# AICat.net
KiCad netlist of a schematic drawn in Altium Designer
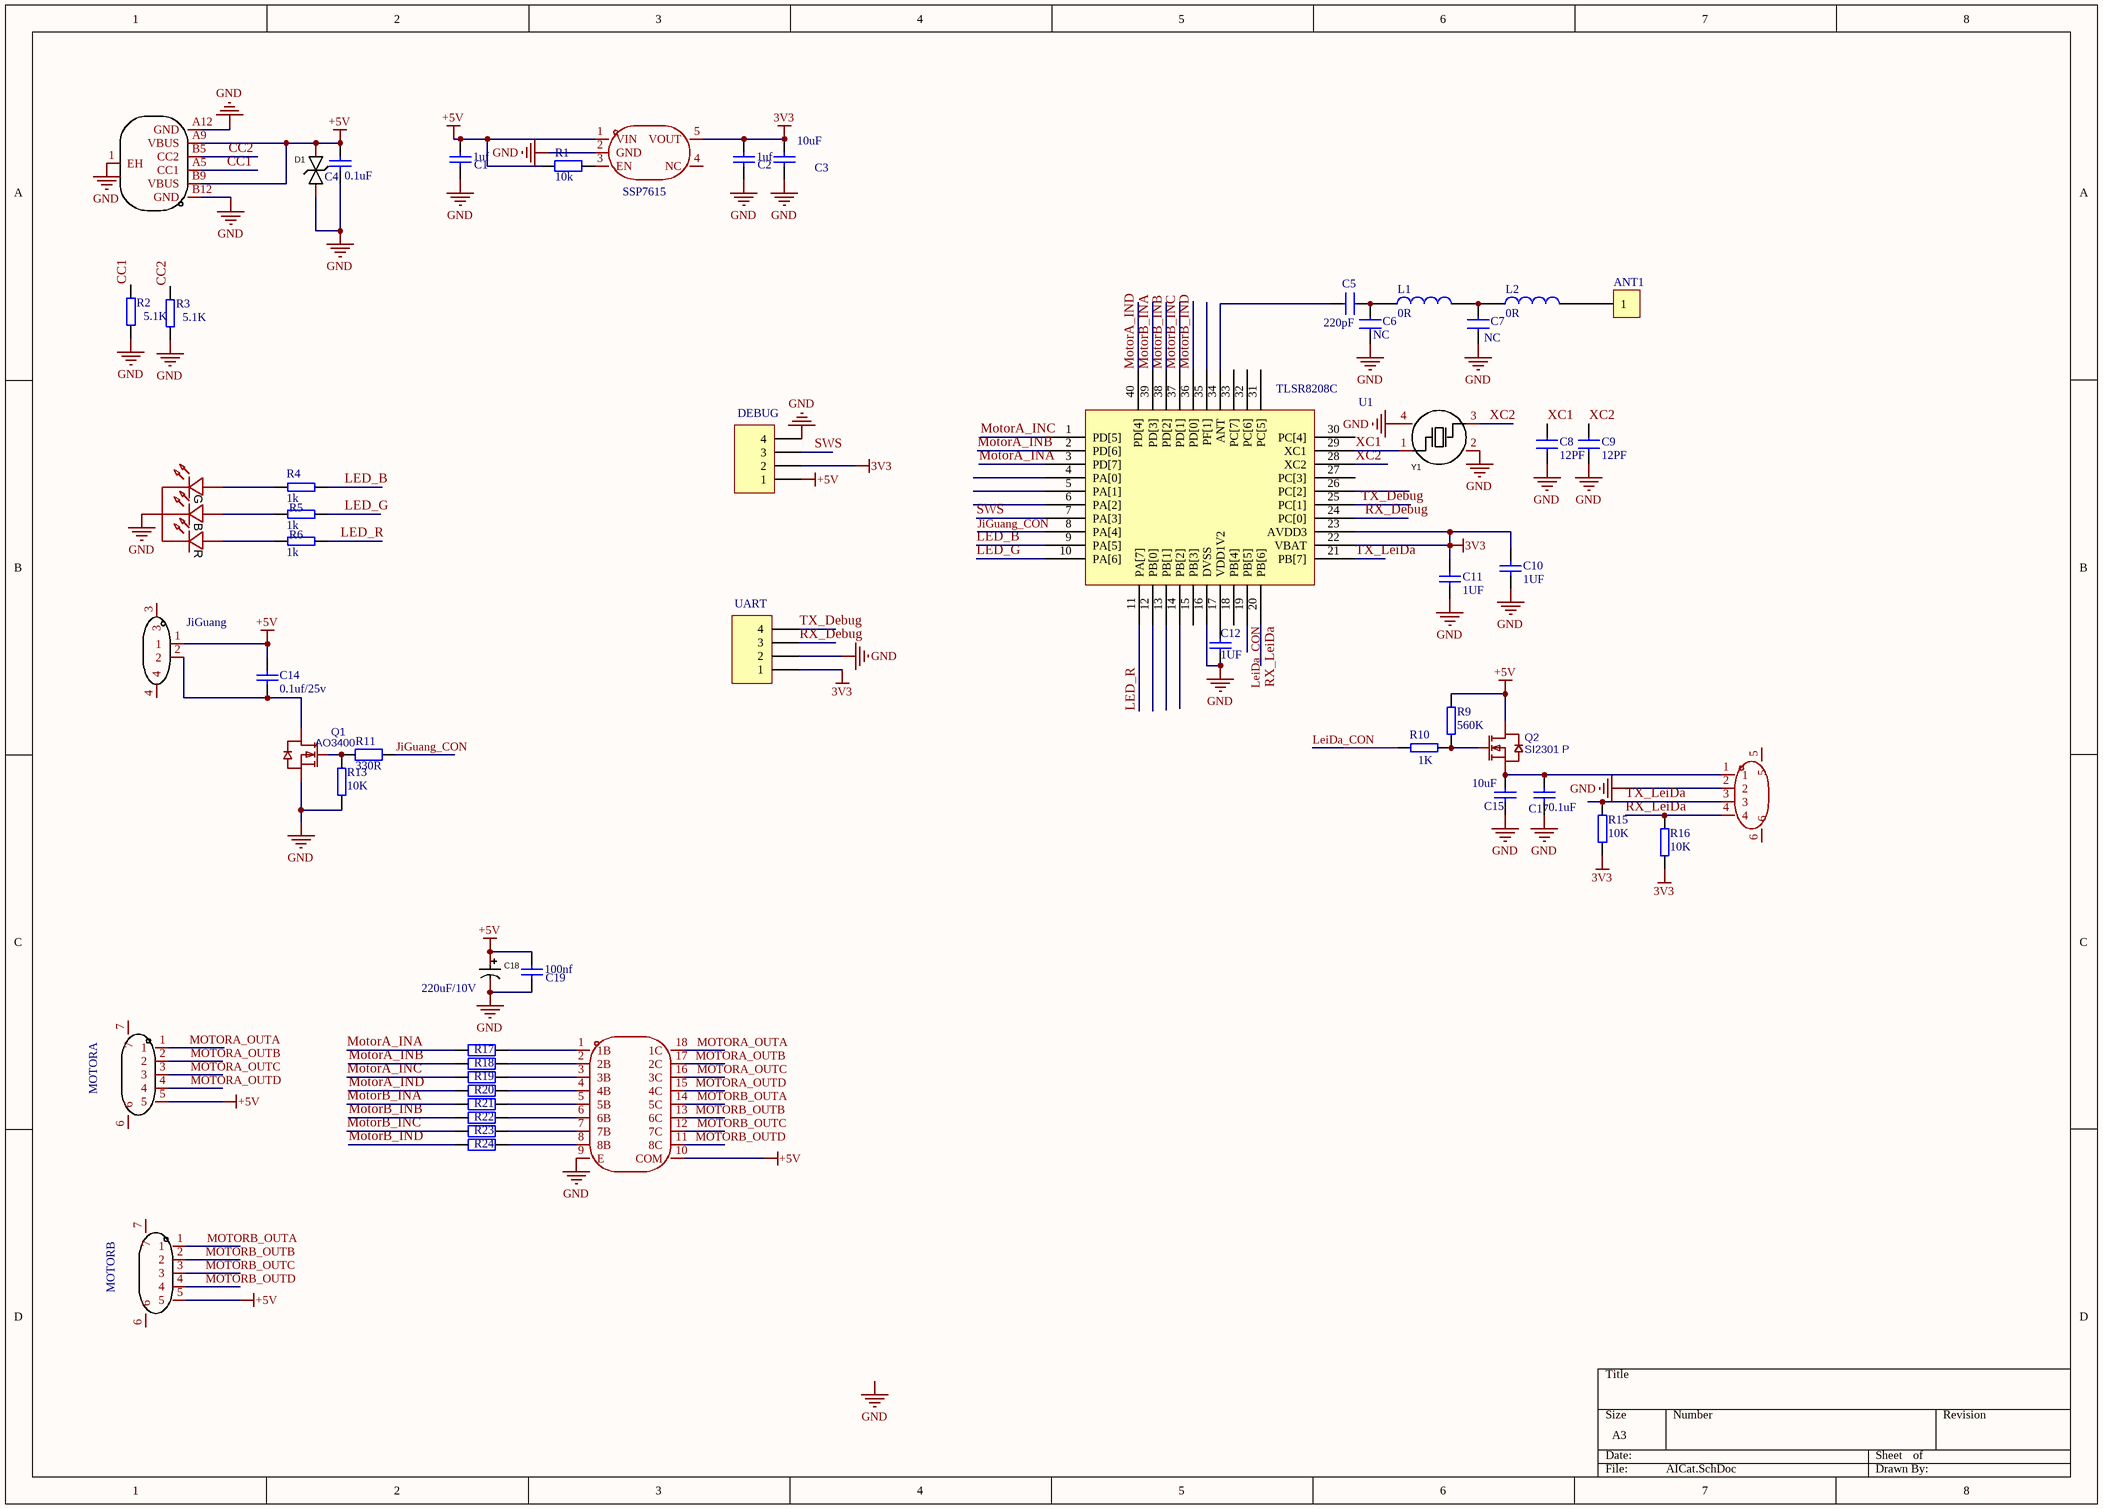
[diagram p0: AICat.SchDoc]

(export (version "E")
  (design (tool "Eeschema 10.0.6"))
  (components
    (comp (ref "ANT1")
      (value "~")
      (footprint "tp")
      (description "Connector")
      (libsource (lib "*") (part "CON1"))
    )
    (comp (ref "C1")
      (value "1uf")
      (footprint "0603_C")
      (description "无极电容")
      (libsource (lib "电容电阻电感保险") (part "Cap1"))
    )
    (comp (ref "C2")
      (value "1uf")
      (footprint "0603_C")
      (description "无极电容")
      (libsource (lib "电容电阻电感保险") (part "Cap1"))
    )
    (comp (ref "C3")
      (value "10uF")
      (footprint "0805_C")
      (description "Capacitor")
      (fields (field (name "PUBLISHER") "Altium Limited"))
      (libsource (lib "*") (part "Cap"))
    )
    (comp (ref "C4")
      (value "0.1uF")
      (footprint "0603_C")
      (description "Capacitor")
      (fields (field (name "PUBLISHER") "Altium Limited"))
      (libsource (lib "*") (part "Cap"))
    )
    (comp (ref "C5")
      (value "220pF")
      (footprint "0603_c")
      (description "Capacitor")
      (libsource (lib "*") (part "CAP"))
    )
    (comp (ref "C6")
      (value "NC")
      (footprint "0603_c")
      (description "Capacitor")
      (libsource (lib "*") (part "CAP"))
    )
    (comp (ref "C7")
      (value "NC")
      (footprint "0603_c")
      (description "Capacitor")
      (libsource (lib "*") (part "CAP"))
    )
    (comp (ref "C8")
      (value "12PF")
      (footprint "0603_c")
      (description "Capacitor")
      (libsource (lib "*") (part "CAP"))
    )
    (comp (ref "C9")
      (value "12PF")
      (footprint "0603_c")
      (description "Capacitor")
      (libsource (lib "*") (part "CAP"))
    )
    (comp (ref "C10") (value "1UF") (footprint "0603_c") (libsource (lib "DIY") (part "CAP")))
    (comp (ref "C11") (value "1UF") (footprint "0603_c") (libsource (lib "DIY") (part "CAP")))
    (comp (ref "C12") (value "1UF") (footprint "0603_c") (libsource (lib "DIY") (part "CAP")))
    (comp (ref "C14")
      (value "0.1uf/25v")
      (footprint "0603_C")
      (description "Capacitor")
      (fields (field (name "PUBLISHER") "Altium Limited"))
      (libsource (lib "*") (part "Cap"))
    )
    (comp (ref "C15")
      (value "10uF")
      (footprint "0805_C")
      (description "Capacitor")
      (fields (field (name "PUBLISHER") "Altium Limited"))
      (libsource (lib "*") (part "Cap"))
    )
    (comp (ref "C17")
      (value "0.1uF")
      (footprint "0603_C")
      (description "Capacitor")
      (fields (field (name "PUBLISHER") "Altium Limited"))
      (libsource (lib "*") (part "Cap"))
    )
    (comp (ref "C18")
      (value "220uF/10V")
      (footprint "SMD 6.3*5.4 电解")
      (fields (field (name "MANUFACTURER PART") "RVT1A221M0605"))
      (libsource (lib "altium-import") (part "root_0_RVT1A221M0605_C72494_"))
    )
    (comp (ref "C19")
      (value "100nf")
      (footprint "0603_C")
      (description "无极电容")
      (libsource (lib "电容电阻电感保险") (part "Cap1"))
    )
    (comp (ref "CN2")
      (value "JiGuang")
      (footprint "CONN-SMD_2P-P1.25-LT")
      (fields (field (name "MANUFACTURER PART") "HC-1.25-2PLT"))
      (libsource (lib "altium-import") (part "root_0_mirrored_HC-1.25-2PLT_"))
    )
    (comp (ref "CN4")
      (value "HC-1.25-4PLT")
      (footprint "CONN-SMD_4P-P1.25_LT")
      (libsource (lib "altium-import") (part "root_0_HC-1.25-4PLT_"))
    )
    (comp (ref "D1")
      (value "SMF5.0CA_C726939")
      (footprint "SOD-123 双向")
      (fields (field (name "MANUFACTURER PART") "SMF5.0CA"))
      (libsource (lib "altium-import") (part "root_1_SMF5.0CA_C726939_"))
    )
    (comp (ref "J1")
      (value "MOTORA")
      (footprint "CONN-SMD_1.25-5PLT")
      (fields (field (name "MANUFACTURER PART") "HC-1.25-5PLT"))
      (libsource (lib "altium-import") (part "root_0_mirrored_HC-1.25-5PLT_"))
    )
    (comp (ref "J2")
      (value "MOTORB")
      (footprint "CONN-SMD_1.25-5PLT")
      (fields (field (name "MANUFACTURER PART") "HC-1.25-5PLT"))
      (libsource (lib "altium-import") (part "root_0_mirrored_HC-1.25-5PLT_"))
    )
    (comp (ref "L1") (value "0R") (footprint "0603_r") (libsource (lib "*") (part "INDUCTOR")))
    (comp (ref "L2") (value "0R") (footprint "0603_r") (libsource (lib "*") (part "INDUCTOR")))
    (comp (ref "LED1")
      (value "MHSC110RGBCT")
      (footprint "LED-SMD_4P-L3.0-W1.5-L")
      (libsource (lib "altium-import") (part "root_3_MHSC110RGBCT_"))
    )
    (comp (ref "P1")
      (value "DEBUG")
      (footprint "SIP4-2.54")
      (description "Header, 4-Pin")
      (fields (field (name "PUBLISHER") "Altium Limited"))
      (libsource (lib "Miscellaneous Connectors") (part "Header 4"))
    )
    (comp (ref "P2")
      (value "UART")
      (footprint "SIP4-2.54")
      (description "Header, 4-Pin")
      (fields (field (name "PUBLISHER") "Altium Limited"))
      (libsource (lib "Miscellaneous Connectors") (part "Header 4"))
    )
    (comp (ref "Q1")
      (value "AO3400")
      (footprint "SOT-23")
      (fields
        (field (name "BOM_SUPPLIER PART") "C2890442")
        (field (name "BOM_MANUFACTURER PART") "JMTL3400A")
        (field (name "CONTRIBUTOR") "LCSC")
      )
      (libsource (lib "altium-import") (part "root_0_mirrored_JMTL3400A_"))
    )
    (comp (ref "Q2")
      (value "SI2301 P")
      (footprint "SOT-23")
      (fields
        (field (name "BOM_SUPPLIER PART") "C2890442")
        (field (name "BOM_MANUFACTURER PART") "JMTL3400A")
        (field (name "CONTRIBUTOR") "LCSC")
      )
      (libsource (lib "altium-import") (part "root_0_JMTL3400A_"))
    )
    (comp (ref "R1")
      (value "10k")
      (footprint "0603_R")
      (description "Resistor")
      (fields (field (name "PUBLISHER") "Altium Limited"))
      (libsource (lib "*") (part "Res2"))
    )
    (comp (ref "R2") (value "5.1K") (footprint "0603_R") (libsource (lib "DIY") (part "RES")))
    (comp (ref "R3") (value "5.1K") (footprint "0603_R") (libsource (lib "DIY") (part "RES")))
    (comp (ref "R4") (value "1k") (footprint "0603_R") (libsource (lib "DIY") (part "RES")))
    (comp (ref "R5") (value "1k") (footprint "0603_R") (libsource (lib "DIY") (part "RES")))
    (comp (ref "R6") (value "1k") (footprint "0603_R") (libsource (lib "DIY") (part "RES")))
    (comp (ref "R9") (value "560K") (footprint "0603_R") (libsource (lib "*") (part "RES")))
    (comp (ref "R10") (value "1K") (footprint "0603_R") (libsource (lib "") (part "RES_1")))
    (comp (ref "R11")
      (value "330R")
      (footprint "0603_R")
      (description "Resistor")
      (fields (field (name "PUBLISHER") "Altium Limited"))
      (libsource (lib "") (part "Res2_2"))
    )
    (comp (ref "R13") (value "10K") (footprint "0603_R") (libsource (lib "DIY") (part "RES")))
    (comp (ref "R15") (value "10K") (footprint "0603_R") (libsource (lib "*") (part "RES")))
    (comp (ref "R16") (value "10K") (footprint "0603_R") (libsource (lib "*") (part "RES")))
    (comp (ref "R17")
      (value "330R")
      (footprint "0603_R")
      (description "Resistor")
      (fields (field (name "PUBLISHER") "Altium Limited"))
      (libsource (lib "") (part "Res2_1"))
    )
    (comp (ref "R18")
      (value "330R")
      (footprint "0603_R")
      (description "Resistor")
      (fields (field (name "PUBLISHER") "Altium Limited"))
      (libsource (lib "") (part "Res2_1"))
    )
    (comp (ref "R19")
      (value "330R")
      (footprint "0603_R")
      (description "Resistor")
      (fields (field (name "PUBLISHER") "Altium Limited"))
      (libsource (lib "") (part "Res2_1"))
    )
    (comp (ref "R20")
      (value "330R")
      (footprint "0603_R")
      (description "Resistor")
      (fields (field (name "PUBLISHER") "Altium Limited"))
      (libsource (lib "") (part "Res2_1"))
    )
    (comp (ref "R21")
      (value "330R")
      (footprint "0603_R")
      (description "Resistor")
      (fields (field (name "PUBLISHER") "Altium Limited"))
      (libsource (lib "") (part "Res2_1"))
    )
    (comp (ref "R22")
      (value "330R")
      (footprint "0603_R")
      (description "Resistor")
      (fields (field (name "PUBLISHER") "Altium Limited"))
      (libsource (lib "") (part "Res2_1"))
    )
    (comp (ref "R23")
      (value "330R")
      (footprint "0603_R")
      (description "Resistor")
      (fields (field (name "PUBLISHER") "Altium Limited"))
      (libsource (lib "") (part "Res2_1"))
    )
    (comp (ref "R24")
      (value "330R")
      (footprint "0603_R")
      (description "Resistor")
      (fields (field (name "PUBLISHER") "Altium Limited"))
      (libsource (lib "") (part "Res2_1"))
    )
    (comp (ref "U1")
      (value "TLSR8208C")
      (footprint "QFN-40_L5.0-W5.0-P0.40-BL-EP3.7")
      (libsource (lib "MyLib") (part "TLSR8208C"))
    )
    (comp (ref "U2")
      (value "ULN2803A")
      (footprint "SOIC-18_L11.6-W7.5-P1.27-LS10.3-BL")
      (libsource (lib "altium-import") (part "root_0_ULN2803A_C181731_"))
    )
    (comp (ref "U4")
      (value "SSP7615")
      (footprint "SOT-23-5")
      (libsource (lib "altium-import") (part "root_0_SSP7615-33M5R_"))
    )
    (comp (ref "USB1")
      (value "TYPE-C 6P")
      (footprint "TPYE-C-6")
      (fields (field (name "MANUFACTURER PART") "TYPE-C 6P LTH6.5"))
      (libsource (lib "altium-import") (part "root_2_TYPE-C 6P LTH6.5_"))
    )
    (comp (ref "Y1")
      (value "24MHz +-20PPM")
      (footprint "CRYSTAL-SMD_4P-L3.2-W2.5")
      (fields (field (name "MANUFACTURER PART") "TAXM13.56M4RLBCCT2T"))
      (libsource (lib "altium-import") (part "root_0_TAXM13.56M4RLBCCT2T_"))
    )
  )
  (nets
    (net (code "1") (name "+5V") (class "Default")
      (node (ref "C1") (pin "2") (pinfunction "2_2") (pintype "passive"))
      (node (ref "C14") (pin "2") (pinfunction "2_2") (pintype "passive"))
      (node (ref "C18") (pin "1") (pinfunction "1_1") (pintype "passive"))
      (node (ref "C19") (pin "2") (pinfunction "2_2") (pintype "passive"))
      (node (ref "C4") (pin "2") (pinfunction "2_2") (pintype "passive"))
      (node (ref "CN2") (pin "1") (pinfunction "1_1") (pintype "passive"))
      (node (ref "D1") (pin "2") (pinfunction "2_2") (pintype "passive"))
      (node (ref "J1") (pin "5") (pinfunction "5_5") (pintype "passive"))
      (node (ref "J2") (pin "5") (pinfunction "5_5") (pintype "passive"))
      (node (ref "P1") (pin "1") (pinfunction "1_1") (pintype "passive"))
      (node (ref "Q2") (pin "2") (pinfunction "D_2") (pintype "passive"))
      (node (ref "R1") (pin "1") (pinfunction "1_1") (pintype "passive"))
      (node (ref "R9") (pin "1") (pintype "passive"))
      (node (ref "U2") (pin "10") (pinfunction "COM_10") (pintype "passive"))
      (node (ref "U4") (pin "1") (pinfunction "VIN_1") (pintype "passive"))
      (node (ref "USB1") (pin "A9") (pinfunction "VBUS_A9") (pintype "passive"))
      (node (ref "USB1") (pin "B9") (pinfunction "VBUS_B9") (pintype "passive"))
    )
    (net (code "2") (name "/CC1") (class "Default")
      (node (ref "R2") (pin "1") (pinfunction "1_1") (pintype "passive"))
      (node (ref "USB1") (pin "A5") (pinfunction "CC1_A5") (pintype "passive"))
    )
    (net (code "3") (name "/CC2") (class "Default")
      (node (ref "R3") (pin "1") (pinfunction "1_1") (pintype "passive"))
      (node (ref "USB1") (pin "B5") (pinfunction "CC2_B5") (pintype "passive"))
    )
    (net (code "4") (name "/JiGuang_CON") (class "Default")
      (node (ref "R11") (pin "2") (pinfunction "2_2") (pintype "passive"))
      (node (ref "U1") (pin "8") (pinfunction "PA[4]_8") (pintype "passive"))
    )
    (net (code "5") (name "/LED_B") (class "Default")
      (node (ref "R4") (pin "2") (pinfunction "2_2") (pintype "passive"))
      (node (ref "U1") (pin "9") (pinfunction "PA[5]_9") (pintype "passive"))
    )
    (net (code "6") (name "/LED_G") (class "Default")
      (node (ref "R5") (pin "2") (pinfunction "2_2") (pintype "passive"))
      (node (ref "U1") (pin "10") (pinfunction "PA[6]_10") (pintype "passive"))
    )
    (net (code "7") (name "/LED_R") (class "Default")
      (node (ref "R6") (pin "2") (pinfunction "2_2") (pintype "passive"))
      (node (ref "U1") (pin "11") (pinfunction "PA[7]_11") (pintype "passive"))
    )
    (net (code "8") (name "/LeiDa_CON") (class "Default")
      (node (ref "R10") (pin "2") (pintype "passive"))
      (node (ref "U1") (pin "19") (pinfunction "PB[5]_19") (pintype "passive"))
    )
    (net (code "9") (name "/MOTORA_OUTA") (class "Default")
      (node (ref "J1") (pin "1") (pinfunction "1_1") (pintype "passive"))
      (node (ref "U2") (pin "18") (pinfunction "1C_18") (pintype "passive"))
    )
    (net (code "10") (name "/MOTORA_OUTB") (class "Default")
      (node (ref "J1") (pin "2") (pinfunction "2_2") (pintype "passive"))
      (node (ref "U2") (pin "17") (pinfunction "2C_17") (pintype "passive"))
    )
    (net (code "11") (name "/MOTORA_OUTC") (class "Default")
      (node (ref "J1") (pin "3") (pinfunction "3_3") (pintype "passive"))
      (node (ref "U2") (pin "16") (pinfunction "3C_16") (pintype "passive"))
    )
    (net (code "12") (name "/MOTORA_OUTD") (class "Default")
      (node (ref "J1") (pin "4") (pinfunction "4_4") (pintype "passive"))
      (node (ref "U2") (pin "15") (pinfunction "4C_15") (pintype "passive"))
    )
    (net (code "13") (name "/MOTORB_OUTA") (class "Default")
      (node (ref "J2") (pin "1") (pinfunction "1_1") (pintype "passive"))
      (node (ref "U2") (pin "14") (pinfunction "5C_14") (pintype "passive"))
    )
    (net (code "14") (name "/MOTORB_OUTB") (class "Default")
      (node (ref "J2") (pin "2") (pinfunction "2_2") (pintype "passive"))
      (node (ref "U2") (pin "13") (pinfunction "6C_13") (pintype "passive"))
    )
    (net (code "15") (name "/MOTORB_OUTC") (class "Default")
      (node (ref "J2") (pin "3") (pinfunction "3_3") (pintype "passive"))
      (node (ref "U2") (pin "12") (pinfunction "7C_12") (pintype "passive"))
    )
    (net (code "16") (name "/MOTORB_OUTD") (class "Default")
      (node (ref "J2") (pin "4") (pinfunction "4_4") (pintype "passive"))
      (node (ref "U2") (pin "11") (pinfunction "8C_11") (pintype "passive"))
    )
    (net (code "17") (name "/MotorA_INA") (class "Default")
      (node (ref "R17") (pin "2") (pinfunction "2_2") (pintype "passive"))
      (node (ref "U1") (pin "3") (pinfunction "PD[7]_3") (pintype "passive"))
    )
    (net (code "18") (name "/MotorA_INB") (class "Default")
      (node (ref "R18") (pin "2") (pinfunction "2_2") (pintype "passive"))
      (node (ref "U1") (pin "2") (pinfunction "PD[6]_2") (pintype "passive"))
    )
    (net (code "19") (name "/MotorA_INC") (class "Default")
      (node (ref "R19") (pin "2") (pinfunction "2_2") (pintype "passive"))
      (node (ref "U1") (pin "1") (pinfunction "PD[5]_1") (pintype "passive"))
    )
    (net (code "20") (name "/MotorA_IND") (class "Default")
      (node (ref "R20") (pin "2") (pinfunction "2_2") (pintype "passive"))
      (node (ref "U1") (pin "40") (pinfunction "PD[4]_40") (pintype "passive"))
    )
    (net (code "21") (name "/MotorB_INA") (class "Default")
      (node (ref "R21") (pin "2") (pinfunction "2_2") (pintype "passive"))
      (node (ref "U1") (pin "39") (pinfunction "PD[3]_39") (pintype "passive"))
    )
    (net (code "22") (name "/MotorB_INB") (class "Default")
      (node (ref "R22") (pin "2") (pinfunction "2_2") (pintype "passive"))
      (node (ref "U1") (pin "38") (pinfunction "PD[2]_38") (pintype "passive"))
    )
    (net (code "23") (name "/MotorB_INC") (class "Default")
      (node (ref "R23") (pin "2") (pinfunction "2_2") (pintype "passive"))
      (node (ref "U1") (pin "37") (pinfunction "PD[1]_37") (pintype "passive"))
    )
    (net (code "24") (name "/MotorB_IND") (class "Default")
      (node (ref "R24") (pin "2") (pinfunction "2_2") (pintype "passive"))
      (node (ref "U1") (pin "36") (pinfunction "PD[0]_36") (pintype "passive"))
    )
    (net (code "25") (name "/RX_Debug") (class "Default")
      (node (ref "P2") (pin "3") (pinfunction "3_3") (pintype "passive"))
      (node (ref "U1") (pin "24") (pinfunction "PC[0]_24") (pintype "passive"))
    )
    (net (code "26") (name "/RX_LeiDa") (class "Default")
      (node (ref "CN4") (pin "4") (pinfunction "4_4") (pintype "passive"))
      (node (ref "R16") (pin "1") (pintype "passive"))
      (node (ref "U1") (pin "20") (pinfunction "PB[6]_20") (pintype "passive"))
    )
    (net (code "27") (name "/SWS") (class "Default")
      (node (ref "P1") (pin "3") (pinfunction "3_3") (pintype "passive"))
      (node (ref "U1") (pin "7") (pinfunction "PA[3]_7") (pintype "passive"))
    )
    (net (code "28") (name "/TX_Debug") (class "Default")
      (node (ref "P2") (pin "4") (pinfunction "4_4") (pintype "passive"))
      (node (ref "U1") (pin "25") (pinfunction "PC[1]_25") (pintype "passive"))
    )
    (net (code "29") (name "/TX_LeiDa") (class "Default")
      (node (ref "CN4") (pin "3") (pinfunction "3_3") (pintype "passive"))
      (node (ref "R15") (pin "1") (pintype "passive"))
      (node (ref "U1") (pin "21") (pinfunction "PB[7]_21") (pintype "passive"))
    )
    (net (code "30") (name "/XC1") (class "Default")
      (node (ref "C8") (pin "2") (pinfunction "2_2") (pintype "passive"))
      (node (ref "U1") (pin "29") (pinfunction "XC1_29") (pintype "passive"))
      (node (ref "Y1") (pin "1") (pinfunction "OSC1_1") (pintype "passive"))
    )
    (net (code "31") (name "/XC2") (class "Default")
      (node (ref "C9") (pin "2") (pinfunction "2_2") (pintype "passive"))
      (node (ref "U1") (pin "28") (pinfunction "XC2_28") (pintype "passive"))
      (node (ref "Y1") (pin "3") (pinfunction "OSC2_3") (pintype "passive"))
    )
    (net (code "32") (name "3V3") (class "Default")
      (node (ref "C10") (pin "1") (pintype "passive"))
      (node (ref "C11") (pin "1") (pintype "passive"))
      (node (ref "C2") (pin "2") (pinfunction "2_2") (pintype "passive"))
      (node (ref "C3") (pin "2") (pinfunction "2_2") (pintype "passive"))
      (node (ref "P1") (pin "2") (pinfunction "2_2") (pintype "passive"))
      (node (ref "P2") (pin "1") (pinfunction "1_1") (pintype "passive"))
      (node (ref "R15") (pin "2") (pintype "passive"))
      (node (ref "R16") (pin "2") (pintype "passive"))
      (node (ref "U1") (pin "22") (pinfunction "VBAT_22") (pintype "passive"))
      (node (ref "U1") (pin "23") (pinfunction "AVDD3_23") (pintype "passive"))
      (node (ref "U4") (pin "5") (pinfunction "VOUT_5") (pintype "passive"))
    )
    (net (code "33") (name "GND") (class "Default")
      (node (ref "C1") (pin "1") (pinfunction "1_1") (pintype "passive"))
      (node (ref "C10") (pin "2") (pintype "passive"))
      (node (ref "C11") (pin "2") (pintype "passive"))
      (node (ref "C12") (pin "1") (pintype "passive"))
      (node (ref "C15") (pin "1") (pinfunction "1_1") (pintype "passive"))
      (node (ref "C17") (pin "1") (pinfunction "1_1") (pintype "passive"))
      (node (ref "C18") (pin "2") (pinfunction "2_2") (pintype "passive"))
      (node (ref "C19") (pin "1") (pinfunction "1_1") (pintype "passive"))
      (node (ref "C2") (pin "1") (pinfunction "1_1") (pintype "passive"))
      (node (ref "C3") (pin "1") (pinfunction "1_1") (pintype "passive"))
      (node (ref "C4") (pin "1") (pinfunction "1_1") (pintype "passive"))
      (node (ref "C6") (pin "1") (pinfunction "1_1") (pintype "passive"))
      (node (ref "C7") (pin "1") (pinfunction "1_1") (pintype "passive"))
      (node (ref "C8") (pin "1") (pinfunction "1_1") (pintype "passive"))
      (node (ref "C9") (pin "1") (pinfunction "1_1") (pintype "passive"))
      (node (ref "CN4") (pin "2") (pinfunction "2_2") (pintype "passive"))
      (node (ref "D1") (pin "1") (pinfunction "1_1") (pintype "passive"))
      (node (ref "LED1") (pin "1") (pinfunction "1_1") (pintype "passive"))
      (node (ref "P1") (pin "4") (pinfunction "4_4") (pintype "passive"))
      (node (ref "P2") (pin "2") (pinfunction "2_2") (pintype "passive"))
      (node (ref "Q1") (pin "2") (pinfunction "S_2") (pintype "passive"))
      (node (ref "R13") (pin "1") (pinfunction "1_1") (pintype "passive"))
      (node (ref "R2") (pin "2") (pinfunction "2_2") (pintype "passive"))
      (node (ref "R3") (pin "2") (pinfunction "2_2") (pintype "passive"))
      (node (ref "U1") (pin "16") (pinfunction "DVSS_16") (pintype "passive"))
      (node (ref "U2") (pin "9") (pinfunction "E_9") (pintype "passive"))
      (node (ref "U4") (pin "2") (pinfunction "GND_2") (pintype "passive"))
      (node (ref "USB1") (pin "1") (pinfunction "EH_1") (pintype "passive"))
      (node (ref "USB1") (pin "A12") (pinfunction "GND_A12") (pintype "passive"))
      (node (ref "USB1") (pin "B12") (pinfunction "GND_B12") (pintype "passive"))
      (node (ref "Y1") (pin "2") (pinfunction "GND_2") (pintype "passive"))
      (node (ref "Y1") (pin "4") (pinfunction "GND_4") (pintype "passive"))
    )
    (net (code "34") (name "Net-(ANT1-Pad1)") (class "Default")
      (node (ref "ANT1") (pin "1") (pinfunction "1_1") (pintype "passive"))
      (node (ref "L2") (pin "2") (pinfunction "2_2") (pintype "passive"))
    )
    (net (code "35") (name "Net-(C5-Pad2)") (class "Default")
      (node (ref "C5") (pin "2") (pinfunction "2_2") (pintype "passive"))
      (node (ref "C6") (pin "2") (pinfunction "2_2") (pintype "passive"))
      (node (ref "L1") (pin "1") (pinfunction "1_1") (pintype "passive"))
    )
    (net (code "36") (name "Net-(C7-Pad2)") (class "Default")
      (node (ref "C7") (pin "2") (pinfunction "2_2") (pintype "passive"))
      (node (ref "L1") (pin "2") (pinfunction "2_2") (pintype "passive"))
      (node (ref "L2") (pin "1") (pinfunction "1_1") (pintype "passive"))
    )
    (net (code "37") (name "Net-(LED1-Pad2)") (class "Default")
      (node (ref "LED1") (pin "2") (pinfunction "2_2") (pintype "passive"))
      (node (ref "R4") (pin "1") (pinfunction "1_1") (pintype "passive"))
    )
    (net (code "38") (name "Net-(LED1-Pad3)") (class "Default")
      (node (ref "LED1") (pin "3") (pinfunction "3_3") (pintype "passive"))
      (node (ref "R5") (pin "1") (pinfunction "1_1") (pintype "passive"))
    )
    (net (code "39") (name "Net-(LED1-Pad4)") (class "Default")
      (node (ref "LED1") (pin "4") (pinfunction "4_4") (pintype "passive"))
      (node (ref "R6") (pin "1") (pinfunction "1_1") (pintype "passive"))
    )
    (net (code "40") (name "Net-(Q1-D)") (class "Default")
      (node (ref "C14") (pin "1") (pinfunction "1_1") (pintype "passive"))
      (node (ref "CN2") (pin "2") (pinfunction "2_2") (pintype "passive"))
      (node (ref "Q1") (pin "3") (pinfunction "D_3") (pintype "passive"))
    )
    (net (code "41") (name "Net-(Q1-G)") (class "Default")
      (node (ref "Q1") (pin "1") (pinfunction "G_1") (pintype "passive"))
      (node (ref "R11") (pin "1") (pinfunction "1_1") (pintype "passive"))
      (node (ref "R13") (pin "2") (pinfunction "2_2") (pintype "passive"))
    )
    (net (code "42") (name "Net-(Q2-G)") (class "Default")
      (node (ref "Q2") (pin "1") (pinfunction "G_1") (pintype "passive"))
      (node (ref "R10") (pin "1") (pintype "passive"))
      (node (ref "R9") (pin "2") (pintype "passive"))
    )
    (net (code "43") (name "Net-(Q2-S)") (class "Default")
      (node (ref "C15") (pin "2") (pinfunction "2_2") (pintype "passive"))
      (node (ref "C17") (pin "2") (pinfunction "2_2") (pintype "passive"))
      (node (ref "CN4") (pin "1") (pinfunction "1_1") (pintype "passive"))
      (node (ref "Q2") (pin "3") (pinfunction "S_3") (pintype "passive"))
    )
    (net (code "44") (name "Net-(U1-ANT)") (class "Default")
      (node (ref "C5") (pin "1") (pinfunction "1_1") (pintype "passive"))
      (node (ref "U1") (pin "34") (pinfunction "ANT_34") (pintype "passive"))
    )
    (net (code "45") (name "Net-(U1-VDD1V2)") (class "Default")
      (node (ref "C12") (pin "2") (pintype "passive"))
      (node (ref "U1") (pin "17") (pinfunction "VDD1V2_17") (pintype "passive"))
    )
    (net (code "46") (name "Net-(U2-1B)") (class "Default")
      (node (ref "R17") (pin "1") (pinfunction "1_1") (pintype "passive"))
      (node (ref "U2") (pin "1") (pinfunction "1B_1") (pintype "passive"))
    )
    (net (code "47") (name "Net-(U2-2B)") (class "Default")
      (node (ref "R18") (pin "1") (pinfunction "1_1") (pintype "passive"))
      (node (ref "U2") (pin "2") (pinfunction "2B_2") (pintype "passive"))
    )
    (net (code "48") (name "Net-(U2-3B)") (class "Default")
      (node (ref "R19") (pin "1") (pinfunction "1_1") (pintype "passive"))
      (node (ref "U2") (pin "3") (pinfunction "3B_3") (pintype "passive"))
    )
    (net (code "49") (name "Net-(U2-4B)") (class "Default")
      (node (ref "R20") (pin "1") (pinfunction "1_1") (pintype "passive"))
      (node (ref "U2") (pin "4") (pinfunction "4B_4") (pintype "passive"))
    )
    (net (code "50") (name "Net-(U2-5B)") (class "Default")
      (node (ref "R21") (pin "1") (pinfunction "1_1") (pintype "passive"))
      (node (ref "U2") (pin "5") (pinfunction "5B_5") (pintype "passive"))
    )
    (net (code "51") (name "Net-(U2-6B)") (class "Default")
      (node (ref "R22") (pin "1") (pinfunction "1_1") (pintype "passive"))
      (node (ref "U2") (pin "6") (pinfunction "6B_6") (pintype "passive"))
    )
    (net (code "52") (name "Net-(U2-7B)") (class "Default")
      (node (ref "R23") (pin "1") (pinfunction "1_1") (pintype "passive"))
      (node (ref "U2") (pin "7") (pinfunction "7B_7") (pintype "passive"))
    )
    (net (code "53") (name "Net-(U2-8B)") (class "Default")
      (node (ref "R24") (pin "1") (pinfunction "1_1") (pintype "passive"))
      (node (ref "U2") (pin "8") (pinfunction "8B_8") (pintype "passive"))
    )
    (net (code "54") (name "Net-(U4-EN)") (class "Default")
      (node (ref "R1") (pin "2") (pinfunction "2_2") (pintype "passive"))
      (node (ref "U4") (pin "3") (pinfunction "EN_3") (pintype "passive"))
    )
    (net (code "55") (name "unconnected-(CN2-Pad3)") (class "Default")
      (node (ref "CN2") (pin "3") (pinfunction "3_3") (pintype "passive"))
    )
    (net (code "56") (name "unconnected-(CN2-Pad4)") (class "Default")
      (node (ref "CN2") (pin "4") (pinfunction "4_4") (pintype "passive"))
    )
    (net (code "57") (name "unconnected-(CN4-Pad5)") (class "Default")
      (node (ref "CN4") (pin "5") (pinfunction "5_5") (pintype "passive"))
    )
    (net (code "58") (name "unconnected-(CN4-Pad6)") (class "Default")
      (node (ref "CN4") (pin "6") (pinfunction "6_6") (pintype "passive"))
    )
    (net (code "59") (name "unconnected-(J1-Pad6)") (class "Default")
      (node (ref "J1") (pin "6") (pinfunction "6_6") (pintype "passive"))
    )
    (net (code "60") (name "unconnected-(J1-Pad7)") (class "Default")
      (node (ref "J1") (pin "7") (pinfunction "7_7") (pintype "passive"))
    )
    (net (code "61") (name "unconnected-(J2-Pad6)") (class "Default")
      (node (ref "J2") (pin "6") (pinfunction "6_6") (pintype "passive"))
    )
    (net (code "62") (name "unconnected-(J2-Pad7)") (class "Default")
      (node (ref "J2") (pin "7") (pinfunction "7_7") (pintype "passive"))
    )
    (net (code "63") (name "unconnected-(U1-PA[0]-Pad4)") (class "Default")
      (node (ref "U1") (pin "4") (pinfunction "PA[0]_4") (pintype "passive"))
    )
    (net (code "64") (name "unconnected-(U1-PA[1]-Pad5)") (class "Default")
      (node (ref "U1") (pin "5") (pinfunction "PA[1]_5") (pintype "passive"))
    )
    (net (code "65") (name "unconnected-(U1-PA[2]-Pad6)") (class "Default")
      (node (ref "U1") (pin "6") (pinfunction "PA[2]_6") (pintype "passive"))
    )
    (net (code "66") (name "unconnected-(U1-PB[0]-Pad12)") (class "Default")
      (node (ref "U1") (pin "12") (pinfunction "PB[0]_12") (pintype "passive"))
    )
    (net (code "67") (name "unconnected-(U1-PB[1]-Pad13)") (class "Default")
      (node (ref "U1") (pin "13") (pinfunction "PB[1]_13") (pintype "passive"))
    )
    (net (code "68") (name "unconnected-(U1-PB[2]-Pad14)") (class "Default")
      (node (ref "U1") (pin "14") (pinfunction "PB[2]_14") (pintype "passive"))
    )
    (net (code "69") (name "unconnected-(U1-PB[3]-Pad15)") (class "Default")
      (node (ref "U1") (pin "15") (pinfunction "PB[3]_15") (pintype "passive"))
    )
    (net (code "70") (name "unconnected-(U1-PB[4]-Pad18)") (class "Default")
      (node (ref "U1") (pin "18") (pinfunction "PB[4]_18") (pintype "passive"))
    )
    (net (code "71") (name "unconnected-(U1-PC[2]-Pad26)") (class "Default")
      (node (ref "U1") (pin "26") (pinfunction "PC[2]_26") (pintype "passive"))
    )
    (net (code "72") (name "unconnected-(U1-PC[3]-Pad27)") (class "Default")
      (node (ref "U1") (pin "27") (pinfunction "PC[3]_27") (pintype "passive"))
    )
    (net (code "73") (name "unconnected-(U1-PC[4]-Pad30)") (class "Default")
      (node (ref "U1") (pin "30") (pinfunction "PC[4]_30") (pintype "passive"))
    )
    (net (code "74") (name "unconnected-(U1-PC[5]-Pad31)") (class "Default")
      (node (ref "U1") (pin "31") (pinfunction "PC[5]_31") (pintype "passive"))
    )
    (net (code "75") (name "unconnected-(U1-PC[6]-Pad32)") (class "Default")
      (node (ref "U1") (pin "32") (pinfunction "PC[6]_32") (pintype "passive"))
    )
    (net (code "76") (name "unconnected-(U1-PC[7]-Pad33)") (class "Default")
      (node (ref "U1") (pin "33") (pinfunction "PC[7]_33") (pintype "passive"))
    )
    (net (code "77") (name "unconnected-(U1-PF[1]-Pad35)") (class "Default")
      (node (ref "U1") (pin "35") (pinfunction "PF[1]_35") (pintype "passive"))
    )
    (net (code "78") (name "unconnected-(U4-NC-Pad4)") (class "Default")
      (node (ref "U4") (pin "4") (pinfunction "NC_4") (pintype "passive"))
    )
  )
)
